# SiLPA_RF_channel.net
KiCad netlist of a schematic drawn in Altium Designer
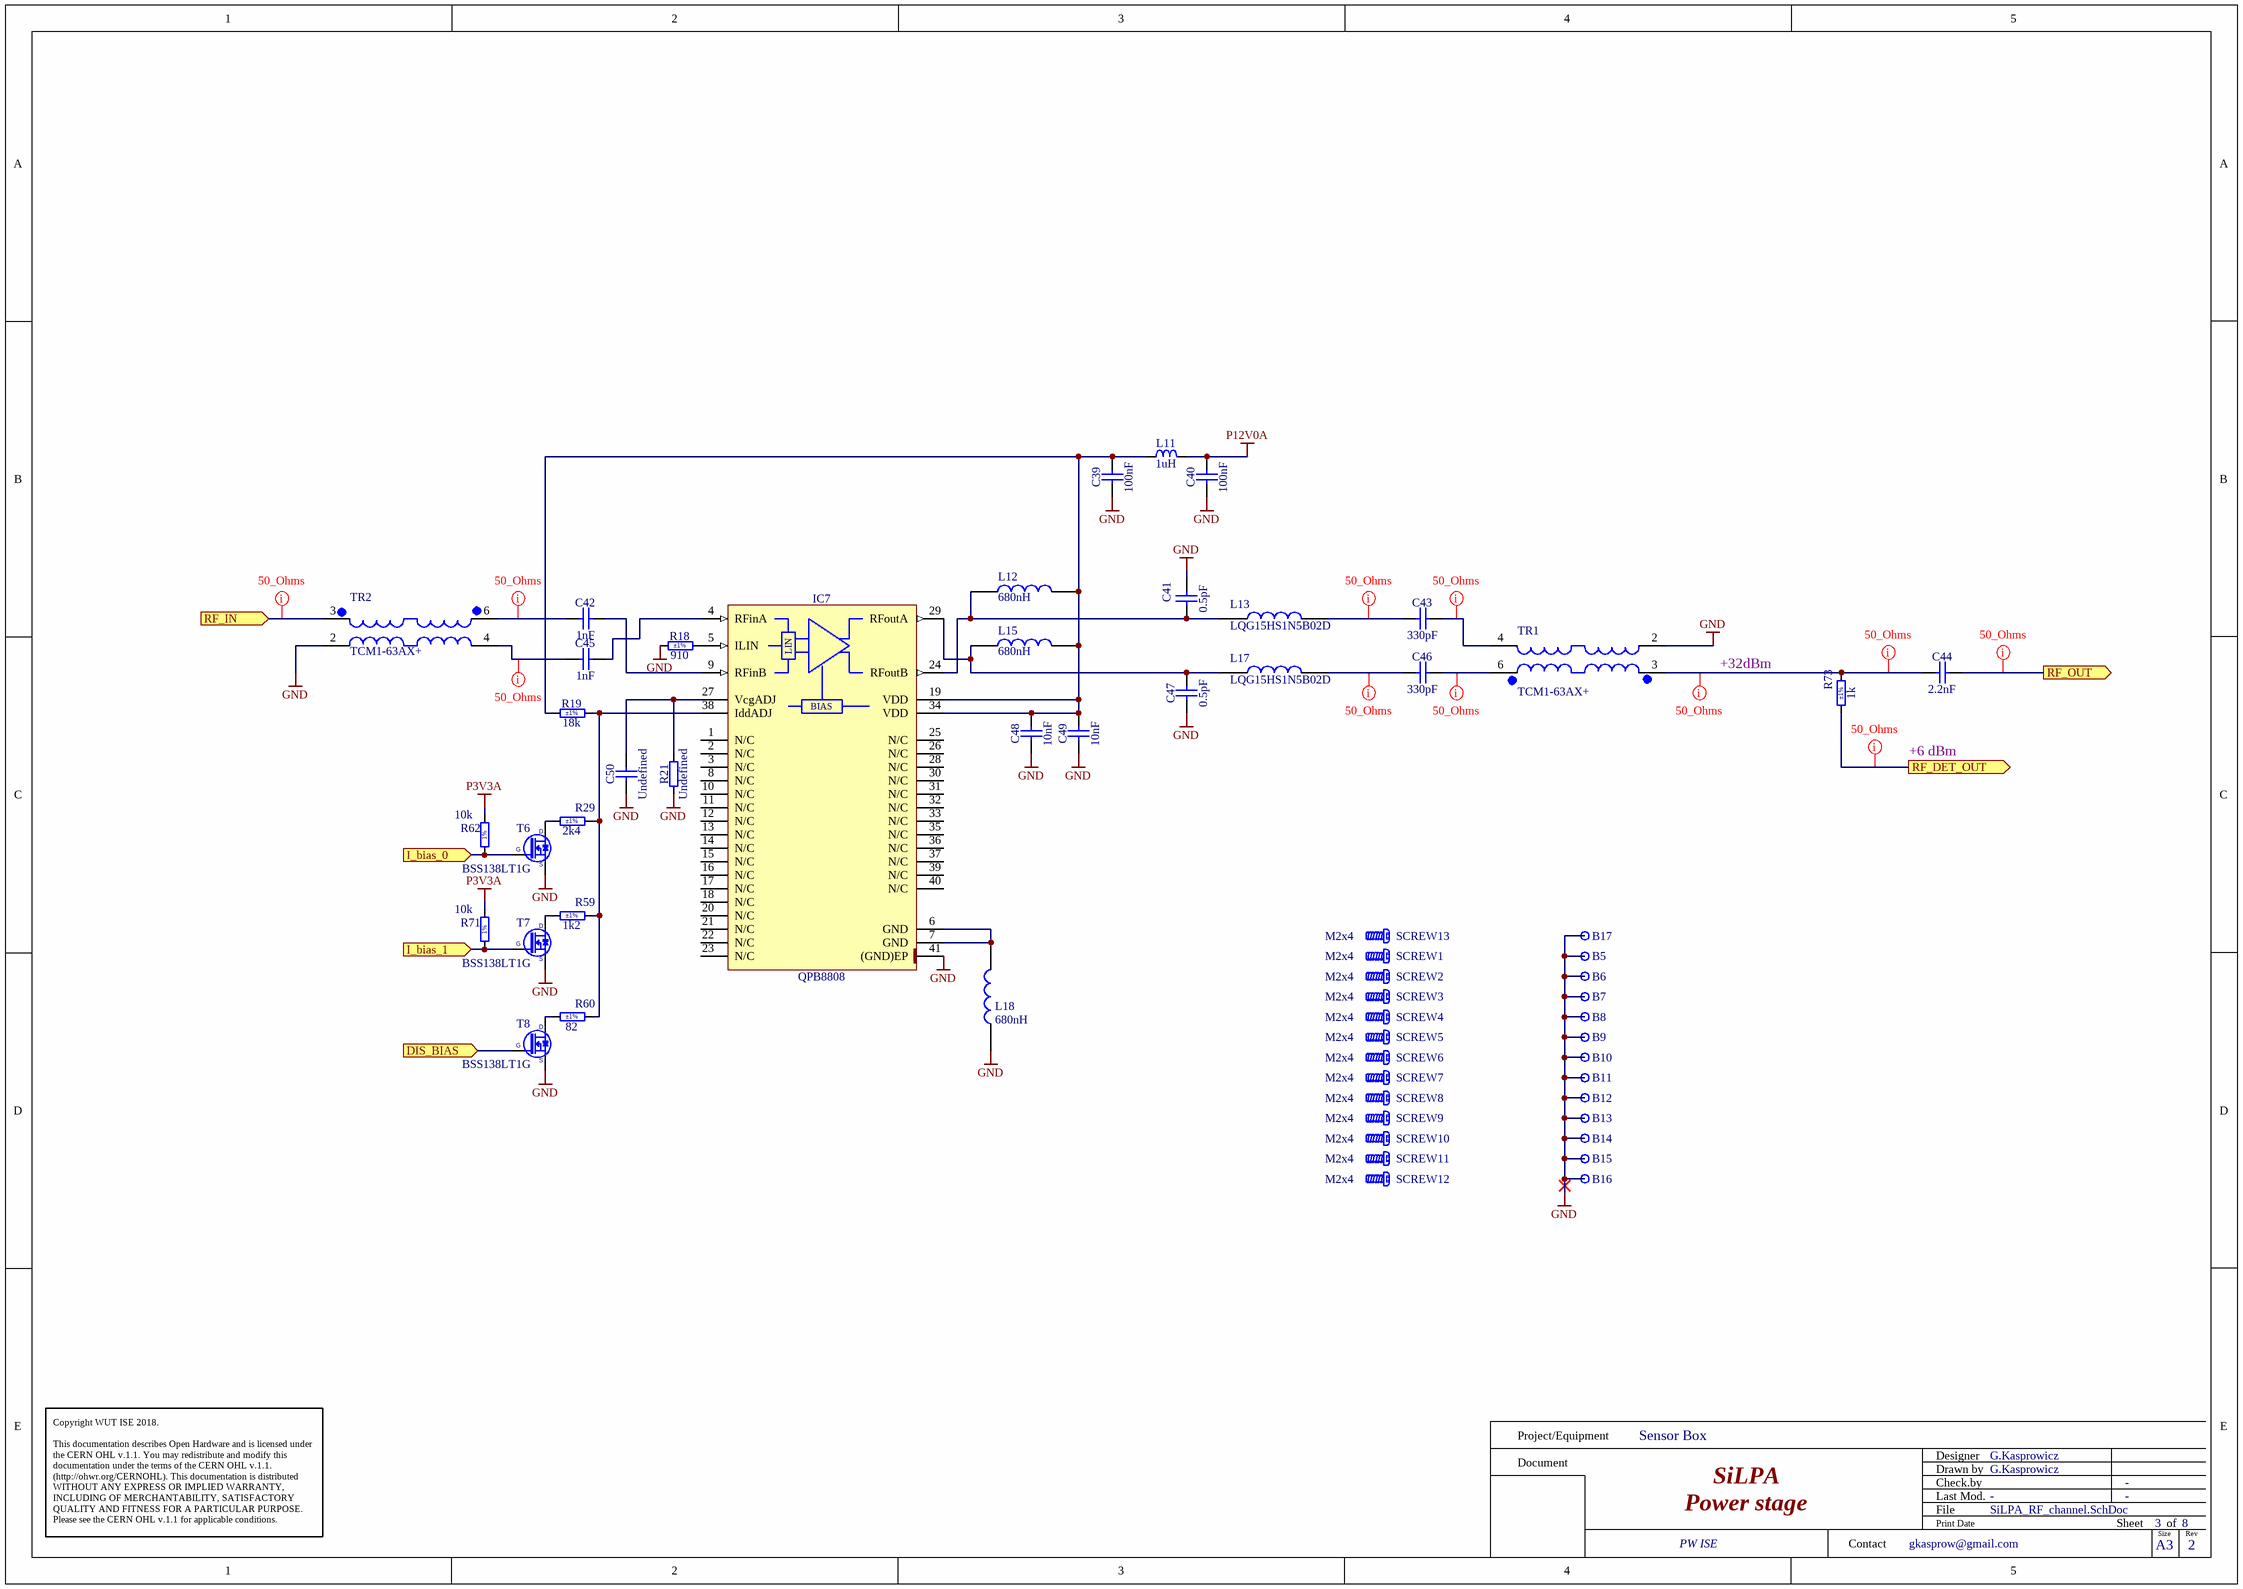
[diagram p0: SiLPA_RF_channel.SchDoc]

(export (version "E")
  (design (tool "Eeschema 10.0.6"))
  (components
    (comp (ref "B5")
      (value "Plated Hole")
      (footprint "MTG240_400")
      (description "Single Terminal Socket")
      (fields (field (name "PART NUMBER") "PLATED_HOLE2.4_PAD4.0") (field (name "AUTHOR") "CERN DEM JMW"))
      (libsource (lib "Eletro-mechanical") (part "Single Terminal Socket"))
    )
    (comp (ref "B6")
      (value "Plated Hole")
      (footprint "MTG240_400")
      (description "Single Terminal Socket")
      (fields (field (name "PART NUMBER") "PLATED_HOLE2.4_PAD4.0") (field (name "AUTHOR") "CERN DEM JMW"))
      (libsource (lib "Eletro-mechanical") (part "Single Terminal Socket"))
    )
    (comp (ref "B7")
      (value "Plated Hole")
      (footprint "MTG240_400")
      (description "Single Terminal Socket")
      (fields (field (name "PART NUMBER") "PLATED_HOLE2.4_PAD4.0") (field (name "AUTHOR") "CERN DEM JMW"))
      (libsource (lib "Eletro-mechanical") (part "Single Terminal Socket"))
    )
    (comp (ref "B8")
      (value "Plated Hole")
      (footprint "MTG240_400")
      (description "Single Terminal Socket")
      (fields (field (name "PART NUMBER") "PLATED_HOLE2.4_PAD4.0") (field (name "AUTHOR") "CERN DEM JMW"))
      (libsource (lib "Eletro-mechanical") (part "Single Terminal Socket"))
    )
    (comp (ref "B9")
      (value "Plated Hole")
      (footprint "MTG240_400")
      (description "Single Terminal Socket")
      (fields (field (name "PART NUMBER") "PLATED_HOLE2.4_PAD4.0") (field (name "AUTHOR") "CERN DEM JMW"))
      (libsource (lib "Eletro-mechanical") (part "Single Terminal Socket"))
    )
    (comp (ref "B10")
      (value "Plated Hole")
      (footprint "MTG240_400")
      (description "Single Terminal Socket")
      (fields (field (name "PART NUMBER") "PLATED_HOLE2.4_PAD4.0") (field (name "AUTHOR") "CERN DEM JMW"))
      (libsource (lib "Eletro-mechanical") (part "Single Terminal Socket"))
    )
    (comp (ref "B11")
      (value "Plated Hole")
      (footprint "MTG240_400")
      (description "Single Terminal Socket")
      (fields (field (name "PART NUMBER") "PLATED_HOLE2.4_PAD4.0") (field (name "AUTHOR") "CERN DEM JMW"))
      (libsource (lib "Eletro-mechanical") (part "Single Terminal Socket"))
    )
    (comp (ref "B12")
      (value "Plated Hole")
      (footprint "MTG240_400")
      (description "Single Terminal Socket")
      (fields (field (name "PART NUMBER") "PLATED_HOLE2.4_PAD4.0") (field (name "AUTHOR") "CERN DEM JMW"))
      (libsource (lib "Eletro-mechanical") (part "Single Terminal Socket"))
    )
    (comp (ref "B13")
      (value "Plated Hole")
      (footprint "MTG240_400")
      (description "Single Terminal Socket")
      (fields (field (name "PART NUMBER") "PLATED_HOLE2.4_PAD4.0") (field (name "AUTHOR") "CERN DEM JMW"))
      (libsource (lib "Eletro-mechanical") (part "Single Terminal Socket"))
    )
    (comp (ref "B14")
      (value "Plated Hole")
      (footprint "MTG240_400")
      (description "Single Terminal Socket")
      (fields (field (name "PART NUMBER") "PLATED_HOLE2.4_PAD4.0") (field (name "AUTHOR") "CERN DEM JMW"))
      (libsource (lib "Eletro-mechanical") (part "Single Terminal Socket"))
    )
    (comp (ref "B15")
      (value "Plated Hole")
      (footprint "MTG240_400")
      (description "Single Terminal Socket")
      (fields (field (name "PART NUMBER") "PLATED_HOLE2.4_PAD4.0") (field (name "AUTHOR") "CERN DEM JMW"))
      (libsource (lib "Eletro-mechanical") (part "Single Terminal Socket"))
    )
    (comp (ref "B16")
      (value "Plated Hole")
      (footprint "MTG240_400")
      (description "Single Terminal Socket")
      (fields (field (name "PART NUMBER") "PLATED_HOLE2.4_PAD4.0") (field (name "AUTHOR") "CERN DEM JMW"))
      (libsource (lib "Eletro-mechanical") (part "Single Terminal Socket"))
    )
    (comp (ref "B17")
      (value "Plated Hole")
      (footprint "MTG240_400")
      (description "Single Terminal Socket")
      (fields (field (name "PART NUMBER") "PLATED_HOLE2.4_PAD4.0") (field (name "AUTHOR") "CERN DEM JMW"))
      (libsource (lib "Eletro-mechanical") (part "Single Terminal Socket"))
    )
    (comp (ref "C39")
      (value "100nF")
      (footprint "CAPC1608X87N")
      (description "Non-polarised capacitor")
      (fields
        (field (name "PART NUMBER") "CC0603_100NF_50V_10%_X7R")
        (field (name "VOLTAGE") "50V")
        (field (name "AUTHOR") "CERN DEM JLC")
      )
      (libsource (lib "Capacitors") (part "Capacitor - non polarized"))
    )
    (comp (ref "C40")
      (value "100nF")
      (footprint "CAPC1608X87N")
      (description "Non-polarised capacitor")
      (fields
        (field (name "PART NUMBER") "CC0603_100NF_50V_10%_X7R")
        (field (name "VOLTAGE") "50V")
        (field (name "AUTHOR") "CERN DEM JLC")
      )
      (libsource (lib "Capacitors") (part "Capacitor - non polarized"))
    )
    (comp (ref "C41")
      (value "0.5pF")
      (footprint "CAPC1608X87N")
      (description "Non-polarised capacitor")
      (fields (field (name "PART NUMBER") "CC0603_0.5PF_50V") (field (name "VOLTAGE") "50V"))
      (libsource (lib "SiLPA") (part "CC0603_0.5PF_50V_WALSIN_HH18N0R5B500CT"))
    )
    (comp (ref "C42")
      (value "1nF")
      (footprint "CAPC1608X90N")
      (description "Non-polarised capacitor")
      (fields
        (field (name "PART NUMBER") "CC0603_1NF_50V_1%_NP0")
        (field (name "VOLTAGE") "50V")
        (field (name "AUTHOR") "CERN DEM JLC")
      )
      (libsource (lib "Capacitors") (part "Capacitor - non polarized"))
    )
    (comp (ref "C43")
      (value "330pF")
      (footprint "CAPC1608X87N")
      (description "Non-polarised capacitor")
      (fields
        (field (name "PART NUMBER") "CC0603_330PF_50V_1%_NP0")
        (field (name "VOLTAGE") "50V")
        (field (name "AUTHOR") "CERN DEM MR")
      )
      (libsource (lib "Capacitors") (part "Capacitor - non polarized"))
    )
    (comp (ref "C44")
      (value "2.2nF")
      (footprint "CAPC1608X87N")
      (description "Non-polarised capacitor")
      (fields
        (field (name "MANUFACTURER") "GENERIC")
        (field (name "MANUFACTURER PART NUMBER") "CC0603_2.2NF_50V_5%_C0G")
        (field (name "AUTHOR") "CERN DEM JMW")
      )
      (libsource (lib "Capacitors") (part "Capacitor - non polarized"))
    )
    (comp (ref "C45")
      (value "1nF")
      (footprint "CAPC1608X90N")
      (description "Non-polarised capacitor")
      (fields
        (field (name "PART NUMBER") "CC0603_1NF_50V_1%_NP0")
        (field (name "VOLTAGE") "50V")
        (field (name "AUTHOR") "CERN DEM JLC")
      )
      (libsource (lib "Capacitors") (part "Capacitor - non polarized"))
    )
    (comp (ref "C46")
      (value "330pF")
      (footprint "CAPC1608X87N")
      (description "Non-polarised capacitor")
      (fields
        (field (name "PART NUMBER") "CC0603_330PF_50V_1%_NP0")
        (field (name "VOLTAGE") "50V")
        (field (name "AUTHOR") "CERN DEM MR")
      )
      (libsource (lib "Capacitors") (part "Capacitor - non polarized"))
    )
    (comp (ref "C47")
      (value "0.5pF")
      (footprint "CAPC1608X87N")
      (description "Non-polarised capacitor")
      (fields (field (name "PART NUMBER") "CC0603_0.5PF_50V") (field (name "VOLTAGE") "50V"))
      (libsource (lib "SiLPA") (part "CC0603_0.5PF_50V_WALSIN_HH18N0R5B500CT"))
    )
    (comp (ref "C48")
      (value "10nF")
      (footprint "CAPC1608X87N")
      (description "Non-polarised capacitor")
      (fields
        (field (name "PART NUMBER") "CC0603_10NF_50V_10%_X7R")
        (field (name "VOLTAGE") "50V")
        (field (name "AUTHOR") "CERN DEM JLC")
      )
      (libsource (lib "Capacitors") (part "Capacitor - non polarized"))
    )
    (comp (ref "C49")
      (value "10nF")
      (footprint "CAPC1608X87N")
      (description "Non-polarised capacitor")
      (fields
        (field (name "PART NUMBER") "CC0603_10NF_50V_10%_X7R")
        (field (name "VOLTAGE") "50V")
        (field (name "AUTHOR") "CERN DEM JLC")
      )
      (libsource (lib "Capacitors") (part "Capacitor - non polarized"))
    )
    (comp (ref "C50")
      (value "Undefined")
      (footprint "CAPC1608X90N")
      (description "Non-polarised capacitor")
      (fields (field (name "PART NUMBER") "CC0603_NO-VALUE") (field (name "AUTHOR") "CERN DEM MR"))
      (libsource (lib "Capacitors") (part "Capacitor - non polarized"))
    )
    (comp (ref "IC7")
      (value "QPB8808")
      (footprint "QFN50P500X700X80-41N-R360X560")
      (description "20 dB CATV +12V Power Doubler")
      (fields (field (name "MANUFACTURER") "QORVO") (field (name "AUTHOR") "CERN DEM BC"))
      (libsource (lib "ICs And Semiconductors") (part "QPB8808"))
    )
    (comp (ref "L11")
      (value "1uH")
      (footprint "INDC2012X110N")
      (description "Inductor")
      (fields
        (field (name "PART NUMBER") "IND0805_1UH_20%_WURTH_74479775210")
        (field (name "POWER") "800mA")
        (field (name "AUTHOR") "CERN DEM JLC")
      )
      (libsource (lib "Inductors & Transformers") (part "Inductor"))
    )
    (comp (ref "L12")
      (value "680nH")
      (footprint "0603AF681XJRW")
      (description "Fixed Inductors 1608 680nH Unshld 5% 490mA 460mOhms")
      (fields
        (field (name "TOLERANCE") "5%")
        (field (name "PART NUMBER") "0603AF-681XJRW")
        (field (name "AUTHORS") "skuchars")
      )
      (libsource (lib "SiLPA") (part "IND0603_COILCRAFT_AF-681XJRW"))
    )
    (comp (ref "L13")
      (value "LQG15HS1N5B02D")
      (footprint "LQG15WH0N7B02D")
      (description "LQG15HS_02 Series Inductor 1.5nH +/-0.1nH 0402 (1005)")
      (fields
        (field (name "POWER") "1000mA")
        (field (name "TOLERANCE") "±0.1nH")
        (field (name "AUTHORS") "skuchars")
      )
      (libsource (lib "SiLPA") (part "LQG15HS1N5B02D"))
    )
    (comp (ref "L15")
      (value "680nH")
      (footprint "0603AF681XJRW")
      (description "Fixed Inductors 1608 680nH Unshld 5% 490mA 460mOhms")
      (fields
        (field (name "TOLERANCE") "5%")
        (field (name "PART NUMBER") "0603AF-681XJRW")
        (field (name "AUTHORS") "skuchars")
      )
      (libsource (lib "SiLPA") (part "IND0603_COILCRAFT_AF-681XJRW"))
    )
    (comp (ref "L17")
      (value "LQG15HS1N5B02D")
      (footprint "LQG15WH0N7B02D")
      (description "LQG15HS_02 Series Inductor 1.5nH +/-0.1nH 0402 (1005)")
      (fields
        (field (name "POWER") "1000mA")
        (field (name "TOLERANCE") "±0.1nH")
        (field (name "AUTHORS") "skuchars")
      )
      (libsource (lib "SiLPA") (part "LQG15HS1N5B02D"))
    )
    (comp (ref "L18")
      (value "680nH")
      (footprint "0603AF681XJRW")
      (description "Fixed Inductors 1608 680nH Unshld 5% 490mA 460mOhms")
      (fields
        (field (name "TOLERANCE") "5%")
        (field (name "PART NUMBER") "0603AF-681XJRW")
        (field (name "AUTHORS") "skuchars")
      )
      (libsource (lib "SiLPA") (part "IND0603_COILCRAFT_AF-681XJRW"))
    )
    (comp (ref "R18")
      (value "910")
      (footprint "RESC1608X55N")
      (description "Resistor - 1%")
      (fields
        (field (name "TOLERANCE") "±1%")
        (field (name "PART NUMBER") "R0603_910R_1%_0.1W_100PPM")
        (field (name "POWER") "0.1W")
        (field (name "AUTHOR") "CERN DEM JLC")
      )
      (libsource (lib "") (part "Resistor - 1%_1"))
    )
    (comp (ref "R19")
      (value "18k")
      (footprint "RESC1005X40N")
      (description "Resistor - 1%")
      (fields
        (field (name "TOLERANCE") "±1%")
        (field (name "PART NUMBER") "R0402_18K_1%_0.0625W_100PPM")
        (field (name "POWER") "0.0625W")
        (field (name "AUTHOR") "CERN DEM JLC")
      )
      (libsource (lib "Resistors") (part "Resistor - 1%"))
    )
    (comp (ref "R21")
      (value "Undefined")
      (footprint "RESC1608X55N")
      (description "Resistor")
      (fields (field (name "PART NUMBER") "R0603_NO-VALUE") (field (name "AUTHOR") "CERN DEM JLC"))
      (libsource (lib "Resistors") (part "Resistor"))
    )
    (comp (ref "R29")
      (value "2k4")
      (footprint "RESC1005X40N")
      (description "Resistor - 1%")
      (fields
        (field (name "TOLERANCE") "±1%")
        (field (name "PART NUMBER") "R0402_2K4_1%_0.0625W_100PPM")
        (field (name "POWER") "0.0625W")
        (field (name "AUTHOR") "CERN DEM JLC")
      )
      (libsource (lib "Resistors") (part "Resistor - 1%"))
    )
    (comp (ref "R59")
      (value "1k2")
      (footprint "RESC1005X40N")
      (description "Resistor - 1%")
      (fields
        (field (name "TOLERANCE") "±1%")
        (field (name "PART NUMBER") "R0402_1K2_1%_0.0625W_100PPM")
        (field (name "POWER") "0.0625W")
        (field (name "AUTHOR") "CERN DEM JLC")
      )
      (libsource (lib "Resistors") (part "Resistor - 1%"))
    )
    (comp (ref "R60")
      (value "82")
      (footprint "RESC1005X40N")
      (description "Resistor - 1%")
      (fields
        (field (name "TOLERANCE") "±1%")
        (field (name "PART NUMBER") "R0402_82R_1%_0.0625W_100PPM")
        (field (name "POWER") "0.0625W")
        (field (name "AUTHOR") "CERN DEM JLC")
      )
      (libsource (lib "Resistors") (part "Resistor - 1%"))
    )
    (comp (ref "R62")
      (value "10k")
      (footprint "RESC1005X40N")
      (description "Resistor - 1%")
      (fields
        (field (name "PART NUMBER") "R0402_10K_1%_0.0625W_100PPM")
        (field (name "POWER") "0.0625W")
        (field (name "AUTHOR") "CERN DEM JLC")
      )
      (libsource (lib "Resistors") (part "Resistor - 1%"))
    )
    (comp (ref "R71")
      (value "10k")
      (footprint "RESC1005X40N")
      (description "Resistor - 1%")
      (fields
        (field (name "PART NUMBER") "R0402_10K_1%_0.0625W_100PPM")
        (field (name "POWER") "0.0625W")
        (field (name "AUTHOR") "CERN DEM JLC")
      )
      (libsource (lib "Resistors") (part "Resistor - 1%"))
    )
    (comp (ref "R73")
      (value "1k")
      (footprint "RESC3216X65N")
      (description "Resistor - 1%")
      (fields
        (field (name "TOLERANCE") "±1%")
        (field (name "PART NUMBER") "R1206_1K_1%_0.25W_100PPM")
        (field (name "POWER") "0.25W")
        (field (name "AUTHOR") "CERN DEM JLC")
      )
      (libsource (lib "") (part "Resistor - 1%_1"))
    )
    (comp (ref "SCREW1")
      (value "M2x4")
      (footprint "BOSSARD_BN5687-3061579_v")
      (description "Screw")
      (fields
        (field (name "PART NUMBER") "BOSSARD_BN5687-3061579_v")
        (field (name "MANUFACTURER") "BOSSARD")
        (field (name "AUTHOR") "CERN DEM JLC")
      )
      (libsource (lib "Eletro-mechanical") (part "Screw"))
    )
    (comp (ref "SCREW2")
      (value "M2x4")
      (footprint "BOSSARD_BN5687-3061579_v")
      (description "Screw")
      (fields
        (field (name "PART NUMBER") "BOSSARD_BN5687-3061579_v")
        (field (name "MANUFACTURER") "BOSSARD")
        (field (name "AUTHOR") "CERN DEM JLC")
      )
      (libsource (lib "Eletro-mechanical") (part "Screw"))
    )
    (comp (ref "SCREW3")
      (value "M2x4")
      (footprint "BOSSARD_BN5687-3061579_v")
      (description "Screw")
      (fields
        (field (name "PART NUMBER") "BOSSARD_BN5687-3061579_v")
        (field (name "MANUFACTURER") "BOSSARD")
        (field (name "AUTHOR") "CERN DEM JLC")
      )
      (libsource (lib "Eletro-mechanical") (part "Screw"))
    )
    (comp (ref "SCREW4")
      (value "M2x4")
      (footprint "BOSSARD_BN5687-3061579_v")
      (description "Screw")
      (fields
        (field (name "PART NUMBER") "BOSSARD_BN5687-3061579_v")
        (field (name "MANUFACTURER") "BOSSARD")
        (field (name "AUTHOR") "CERN DEM JLC")
      )
      (libsource (lib "Eletro-mechanical") (part "Screw"))
    )
    (comp (ref "SCREW5")
      (value "M2x4")
      (footprint "BOSSARD_BN5687-3061579_v")
      (description "Screw")
      (fields
        (field (name "PART NUMBER") "BOSSARD_BN5687-3061579_v")
        (field (name "MANUFACTURER") "BOSSARD")
        (field (name "AUTHOR") "CERN DEM JLC")
      )
      (libsource (lib "Eletro-mechanical") (part "Screw"))
    )
    (comp (ref "SCREW6")
      (value "M2x4")
      (footprint "BOSSARD_BN5687-3061579_v")
      (description "Screw")
      (fields
        (field (name "PART NUMBER") "BOSSARD_BN5687-3061579_v")
        (field (name "MANUFACTURER") "BOSSARD")
        (field (name "AUTHOR") "CERN DEM JLC")
      )
      (libsource (lib "Eletro-mechanical") (part "Screw"))
    )
    (comp (ref "SCREW7")
      (value "M2x4")
      (footprint "BOSSARD_BN5687-3061579_v")
      (description "Screw")
      (fields
        (field (name "PART NUMBER") "BOSSARD_BN5687-3061579_v")
        (field (name "MANUFACTURER") "BOSSARD")
        (field (name "AUTHOR") "CERN DEM JLC")
      )
      (libsource (lib "Eletro-mechanical") (part "Screw"))
    )
    (comp (ref "SCREW8")
      (value "M2x4")
      (footprint "BOSSARD_BN5687-3061579_v")
      (description "Screw")
      (fields
        (field (name "PART NUMBER") "BOSSARD_BN5687-3061579_v")
        (field (name "MANUFACTURER") "BOSSARD")
        (field (name "AUTHOR") "CERN DEM JLC")
      )
      (libsource (lib "Eletro-mechanical") (part "Screw"))
    )
    (comp (ref "SCREW9")
      (value "M2x4")
      (footprint "BOSSARD_BN5687-3061579_v")
      (description "Screw")
      (fields
        (field (name "PART NUMBER") "BOSSARD_BN5687-3061579_v")
        (field (name "MANUFACTURER") "BOSSARD")
        (field (name "AUTHOR") "CERN DEM JLC")
      )
      (libsource (lib "Eletro-mechanical") (part "Screw"))
    )
    (comp (ref "SCREW10")
      (value "M2x4")
      (footprint "BOSSARD_BN5687-3061579_v")
      (description "Screw")
      (fields
        (field (name "PART NUMBER") "BOSSARD_BN5687-3061579_v")
        (field (name "MANUFACTURER") "BOSSARD")
        (field (name "AUTHOR") "CERN DEM JLC")
      )
      (libsource (lib "Eletro-mechanical") (part "Screw"))
    )
    (comp (ref "SCREW11")
      (value "M2x4")
      (footprint "BOSSARD_BN5687-3061579_v")
      (description "Screw")
      (fields
        (field (name "PART NUMBER") "BOSSARD_BN5687-3061579_v")
        (field (name "MANUFACTURER") "BOSSARD")
        (field (name "AUTHOR") "CERN DEM JLC")
      )
      (libsource (lib "Eletro-mechanical") (part "Screw"))
    )
    (comp (ref "SCREW12")
      (value "M2x4")
      (footprint "BOSSARD_BN5687-3061579_v")
      (description "Screw")
      (fields
        (field (name "PART NUMBER") "BOSSARD_BN5687-3061579_v")
        (field (name "MANUFACTURER") "BOSSARD")
        (field (name "AUTHOR") "CERN DEM JLC")
      )
      (libsource (lib "Eletro-mechanical") (part "Screw"))
    )
    (comp (ref "SCREW13")
      (value "M2x4")
      (footprint "BOSSARD_BN5687-3061579_v")
      (description "Screw")
      (fields
        (field (name "PART NUMBER") "BOSSARD_BN5687-3061579_v")
        (field (name "MANUFACTURER") "BOSSARD")
        (field (name "AUTHOR") "CERN DEM JLC")
      )
      (libsource (lib "Eletro-mechanical") (part "Screw"))
    )
    (comp (ref "T6")
      (value "BSS138LT1G")
      (footprint "SOT95P240X110-3N")
      (description "N-CHANNEL MOSFET WITH DIODE")
      (fields (field (name "MANUFACTURER") "ON SEMICONDUCTOR") (field (name "AUTHOR") "CERN DEM JLC"))
      (libsource (lib "ICs And Semiconductors") (part "N-MOSFET-D 1G 2S 3D"))
    )
    (comp (ref "T7")
      (value "BSS138LT1G")
      (footprint "SOT95P240X110-3N")
      (description "N-CHANNEL MOSFET WITH DIODE")
      (fields (field (name "MANUFACTURER") "ON SEMICONDUCTOR") (field (name "AUTHOR") "CERN DEM JLC"))
      (libsource (lib "ICs And Semiconductors") (part "N-MOSFET-D 1G 2S 3D"))
    )
    (comp (ref "T8")
      (value "BSS138LT1G")
      (footprint "SOT95P240X110-3N")
      (description "N-CHANNEL MOSFET WITH DIODE")
      (fields (field (name "MANUFACTURER") "ON SEMICONDUCTOR") (field (name "AUTHOR") "CERN DEM JLC"))
      (libsource (lib "ICs And Semiconductors") (part "N-MOSFET-D 1G 2S 3D"))
    )
    (comp (ref "TR1")
      (value "TCM1-63AX+")
      (footprint "SiLPA:XFMR_TCM1-63AX+")
      (description "1:1 CORE & WIRE Transformer, 10 - 6000 MHz, 50Ω")
      (fields
        (field (name "MANUFACTURER") "Mini-Circuits")
        (field (name "POWER") "0.2W")
        (field (name "AUTHORS") "skuchars")
      )
      (libsource (lib "SiLPA") (part "TCM1-63AX+"))
    )
    (comp (ref "TR2")
      (value "TCM1-63AX+")
      (footprint "SiLPA:XFMR_TCM1-63AX+")
      (description "1:1 CORE & WIRE Transformer, 10 - 6000 MHz, 50Ω")
      (fields
        (field (name "MANUFACTURER") "Mini-Circuits")
        (field (name "POWER") "0.2W")
        (field (name "AUTHORS") "skuchars")
      )
      (libsource (lib "") (part "TCM1-63AX+_1"))
    )
  )
  (nets
    (net (code "1") (name "/DIS_BIAS") (class "Default")
      (node (ref "T8") (pin "1") (pinfunction "G_1") (pintype "passive"))
    )
    (net (code "2") (name "/I_bias_0") (class "Default")
      (node (ref "R62") (pin "1") (pinfunction "1_1") (pintype "passive"))
      (node (ref "T6") (pin "1") (pinfunction "G_1") (pintype "passive"))
    )
    (net (code "3") (name "/I_bias_1") (class "Default")
      (node (ref "R71") (pin "1") (pinfunction "1_1") (pintype "passive"))
      (node (ref "T7") (pin "1") (pinfunction "G_1") (pintype "passive"))
    )
    (net (code "4") (name "/RF_DET_OUT") (class "Default")
      (node (ref "R73") (pin "1") (pinfunction "1_1") (pintype "passive"))
    )
    (net (code "5") (name "/RF_IN") (class "Default")
      (node (ref "TR2") (pin "3") (pinfunction "3_3") (pintype "passive"))
    )
    (net (code "6") (name "/RF_OUT") (class "Default")
      (node (ref "C44") (pin "2") (pinfunction "2_2") (pintype "passive"))
    )
    (net (code "7") (name "GND") (class "Default")
      (node (ref "B10") (pin "1") (pinfunction "1_1") (pintype "bidirectional"))
      (node (ref "B11") (pin "1") (pinfunction "1_1") (pintype "bidirectional"))
      (node (ref "B12") (pin "1") (pinfunction "1_1") (pintype "bidirectional"))
      (node (ref "B13") (pin "1") (pinfunction "1_1") (pintype "bidirectional"))
      (node (ref "B14") (pin "1") (pinfunction "1_1") (pintype "bidirectional"))
      (node (ref "B15") (pin "1") (pinfunction "1_1") (pintype "bidirectional"))
      (node (ref "B16") (pin "1") (pinfunction "1_1") (pintype "bidirectional"))
      (node (ref "B17") (pin "1") (pinfunction "1_1") (pintype "bidirectional"))
      (node (ref "B5") (pin "1") (pinfunction "1_1") (pintype "bidirectional"))
      (node (ref "B6") (pin "1") (pinfunction "1_1") (pintype "bidirectional"))
      (node (ref "B7") (pin "1") (pinfunction "1_1") (pintype "bidirectional"))
      (node (ref "B8") (pin "1") (pinfunction "1_1") (pintype "bidirectional"))
      (node (ref "B9") (pin "1") (pinfunction "1_1") (pintype "bidirectional"))
      (node (ref "C39") (pin "1") (pinfunction "1_1") (pintype "passive"))
      (node (ref "C40") (pin "1") (pinfunction "1_1") (pintype "passive"))
      (node (ref "C41") (pin "2") (pinfunction "2_2") (pintype "passive"))
      (node (ref "C47") (pin "1") (pinfunction "1_1") (pintype "passive"))
      (node (ref "C48") (pin "1") (pinfunction "1_1") (pintype "passive"))
      (node (ref "C49") (pin "1") (pinfunction "1_1") (pintype "passive"))
      (node (ref "C50") (pin "1") (pinfunction "1_1") (pintype "passive"))
      (node (ref "IC7") (pin "41") (pinfunction "(GND)EP_41") (pintype "power_in"))
      (node (ref "L18") (pin "1") (pinfunction "1_1") (pintype "passive"))
      (node (ref "R18") (pin "1") (pinfunction "1_1") (pintype "passive"))
      (node (ref "R21") (pin "1") (pinfunction "1_1") (pintype "passive"))
      (node (ref "T6") (pin "2") (pinfunction "S_2") (pintype "passive"))
      (node (ref "T7") (pin "2") (pinfunction "S_2") (pintype "passive"))
      (node (ref "T8") (pin "2") (pinfunction "S_2") (pintype "passive"))
      (node (ref "TR1") (pin "2") (pinfunction "2_2") (pintype "passive"))
      (node (ref "TR2") (pin "2") (pinfunction "2_2") (pintype "passive"))
    )
    (net (code "8") (name "Net-(C39-Pad2)") (class "Default")
      (node (ref "C39") (pin "2") (pinfunction "2_2") (pintype "passive"))
      (node (ref "C48") (pin "2") (pinfunction "2_2") (pintype "passive"))
      (node (ref "C49") (pin "2") (pinfunction "2_2") (pintype "passive"))
      (node (ref "IC7") (pin "19") (pinfunction "VDD_19") (pintype "power_in"))
      (node (ref "IC7") (pin "34") (pinfunction "VDD_34") (pintype "power_in"))
      (node (ref "L11") (pin "1") (pinfunction "1_1") (pintype "passive"))
      (node (ref "L12") (pin "2") (pinfunction "2_2") (pintype "passive"))
      (node (ref "L15") (pin "2") (pinfunction "2_2") (pintype "passive"))
      (node (ref "R19") (pin "1") (pinfunction "1_1") (pintype "passive"))
    )
    (net (code "9") (name "Net-(C42-Pad1)") (class "Default")
      (node (ref "C42") (pin "1") (pinfunction "1_1") (pintype "passive"))
      (node (ref "TR2") (pin "6") (pinfunction "6_6") (pintype "passive"))
    )
    (net (code "10") (name "Net-(C43-Pad1)") (class "Default")
      (node (ref "C43") (pin "1") (pinfunction "1_1") (pintype "passive"))
      (node (ref "L13") (pin "2") (pinfunction "2_2") (pintype "passive"))
    )
    (net (code "11") (name "Net-(C43-Pad2)") (class "Default")
      (node (ref "C43") (pin "2") (pinfunction "2_2") (pintype "passive"))
      (node (ref "TR1") (pin "4") (pinfunction "4_4") (pintype "passive"))
    )
    (net (code "12") (name "Net-(C44-Pad1)") (class "Default")
      (node (ref "C44") (pin "1") (pinfunction "1_1") (pintype "passive"))
      (node (ref "R73") (pin "2") (pinfunction "2_2") (pintype "passive"))
      (node (ref "TR1") (pin "3") (pinfunction "3_3") (pintype "passive"))
    )
    (net (code "13") (name "Net-(C45-Pad1)") (class "Default")
      (node (ref "C45") (pin "1") (pinfunction "1_1") (pintype "passive"))
      (node (ref "TR2") (pin "4") (pinfunction "4_4") (pintype "passive"))
    )
    (net (code "14") (name "Net-(C46-Pad1)") (class "Default")
      (node (ref "C46") (pin "1") (pinfunction "1_1") (pintype "passive"))
      (node (ref "L17") (pin "2") (pinfunction "2_2") (pintype "passive"))
    )
    (net (code "15") (name "Net-(C46-Pad2)") (class "Default")
      (node (ref "C46") (pin "2") (pinfunction "2_2") (pintype "passive"))
      (node (ref "TR1") (pin "6") (pinfunction "6_6") (pintype "passive"))
    )
    (net (code "16") (name "Net-(IC7-GND-Pad6)") (class "Default")
      (node (ref "IC7") (pin "6") (pinfunction "GND_6") (pintype "power_in"))
      (node (ref "IC7") (pin "7") (pinfunction "GND_7") (pintype "power_in"))
      (node (ref "L18") (pin "2") (pinfunction "2_2") (pintype "passive"))
    )
    (net (code "17") (name "Net-(IC7-ILIN)") (class "Default")
      (node (ref "IC7") (pin "5") (pinfunction "ILIN_5") (pintype "input"))
      (node (ref "R18") (pin "2") (pinfunction "2_2") (pintype "passive"))
    )
    (net (code "18") (name "Net-(IC7-IddADJ)") (class "Default")
      (node (ref "IC7") (pin "38") (pinfunction "IddADJ_38") (pintype "power_in"))
      (node (ref "R19") (pin "2") (pinfunction "2_2") (pintype "passive"))
      (node (ref "R29") (pin "2") (pinfunction "2_2") (pintype "passive"))
      (node (ref "R59") (pin "2") (pinfunction "2_2") (pintype "passive"))
      (node (ref "R60") (pin "2") (pinfunction "2_2") (pintype "passive"))
    )
    (net (code "19") (name "Net-(IC7-RFinA)") (class "Default")
      (node (ref "C45") (pin "2") (pinfunction "2_2") (pintype "passive"))
      (node (ref "IC7") (pin "4") (pinfunction "RFinA_4") (pintype "input"))
    )
    (net (code "20") (name "Net-(IC7-RFinB)") (class "Default")
      (node (ref "C42") (pin "2") (pinfunction "2_2") (pintype "passive"))
      (node (ref "IC7") (pin "9") (pinfunction "RFinB_9") (pintype "input"))
    )
    (net (code "21") (name "Net-(IC7-RFoutA)") (class "Default")
      (node (ref "C47") (pin "2") (pinfunction "2_2") (pintype "passive"))
      (node (ref "IC7") (pin "29") (pinfunction "RFoutA_29") (pintype "output"))
      (node (ref "L15") (pin "1") (pinfunction "1_1") (pintype "passive"))
      (node (ref "L17") (pin "1") (pinfunction "1_1") (pintype "passive"))
    )
    (net (code "22") (name "Net-(IC7-RFoutB)") (class "Default")
      (node (ref "C41") (pin "1") (pinfunction "1_1") (pintype "passive"))
      (node (ref "IC7") (pin "24") (pinfunction "RFoutB_24") (pintype "output"))
      (node (ref "L12") (pin "1") (pinfunction "1_1") (pintype "passive"))
      (node (ref "L13") (pin "1") (pinfunction "1_1") (pintype "passive"))
    )
    (net (code "23") (name "Net-(IC7-VcgADJ)") (class "Default")
      (node (ref "C50") (pin "2") (pinfunction "2_2") (pintype "passive"))
      (node (ref "IC7") (pin "27") (pinfunction "VcgADJ_27") (pintype "power_in"))
      (node (ref "R21") (pin "2") (pinfunction "2_2") (pintype "passive"))
    )
    (net (code "24") (name "Net-(T6-D)") (class "Default")
      (node (ref "R29") (pin "1") (pinfunction "1_1") (pintype "passive"))
      (node (ref "T6") (pin "3") (pinfunction "D_3") (pintype "passive"))
    )
    (net (code "25") (name "Net-(T7-D)") (class "Default")
      (node (ref "R59") (pin "1") (pinfunction "1_1") (pintype "passive"))
      (node (ref "T7") (pin "3") (pinfunction "D_3") (pintype "passive"))
    )
    (net (code "26") (name "Net-(T8-D)") (class "Default")
      (node (ref "R60") (pin "1") (pinfunction "1_1") (pintype "passive"))
      (node (ref "T8") (pin "3") (pinfunction "D_3") (pintype "passive"))
    )
    (net (code "27") (name "P3V3A") (class "Default")
      (node (ref "R62") (pin "2") (pinfunction "2_2") (pintype "passive"))
      (node (ref "R71") (pin "2") (pinfunction "2_2") (pintype "passive"))
    )
    (net (code "28") (name "P12V0A") (class "Default")
      (node (ref "C40") (pin "2") (pinfunction "2_2") (pintype "passive"))
      (node (ref "L11") (pin "2") (pinfunction "2_2") (pintype "passive"))
    )
    (net (code "29") (name "unconnected-(IC7-N{slash}C-Pad1)") (class "Default")
      (node (ref "IC7") (pin "1") (pinfunction "N/C_1") (pintype "passive"))
    )
    (net (code "30") (name "unconnected-(IC7-N{slash}C-Pad2)") (class "Default")
      (node (ref "IC7") (pin "2") (pinfunction "N/C_2") (pintype "passive"))
    )
    (net (code "31") (name "unconnected-(IC7-N{slash}C-Pad3)") (class "Default")
      (node (ref "IC7") (pin "3") (pinfunction "N/C_3") (pintype "passive"))
    )
    (net (code "32") (name "unconnected-(IC7-N{slash}C-Pad8)") (class "Default")
      (node (ref "IC7") (pin "8") (pinfunction "N/C_8") (pintype "passive"))
    )
    (net (code "33") (name "unconnected-(IC7-N{slash}C-Pad10)") (class "Default")
      (node (ref "IC7") (pin "10") (pinfunction "N/C_10") (pintype "passive"))
    )
    (net (code "34") (name "unconnected-(IC7-N{slash}C-Pad11)") (class "Default")
      (node (ref "IC7") (pin "11") (pinfunction "N/C_11") (pintype "passive"))
    )
    (net (code "35") (name "unconnected-(IC7-N{slash}C-Pad12)") (class "Default")
      (node (ref "IC7") (pin "12") (pinfunction "N/C_12") (pintype "passive"))
    )
    (net (code "36") (name "unconnected-(IC7-N{slash}C-Pad13)") (class "Default")
      (node (ref "IC7") (pin "13") (pinfunction "N/C_13") (pintype "passive"))
    )
    (net (code "37") (name "unconnected-(IC7-N{slash}C-Pad14)") (class "Default")
      (node (ref "IC7") (pin "14") (pinfunction "N/C_14") (pintype "passive"))
    )
    (net (code "38") (name "unconnected-(IC7-N{slash}C-Pad15)") (class "Default")
      (node (ref "IC7") (pin "15") (pinfunction "N/C_15") (pintype "passive"))
    )
    (net (code "39") (name "unconnected-(IC7-N{slash}C-Pad16)") (class "Default")
      (node (ref "IC7") (pin "16") (pinfunction "N/C_16") (pintype "passive"))
    )
    (net (code "40") (name "unconnected-(IC7-N{slash}C-Pad17)") (class "Default")
      (node (ref "IC7") (pin "17") (pinfunction "N/C_17") (pintype "passive"))
    )
    (net (code "41") (name "unconnected-(IC7-N{slash}C-Pad18)") (class "Default")
      (node (ref "IC7") (pin "18") (pinfunction "N/C_18") (pintype "passive"))
    )
    (net (code "42") (name "unconnected-(IC7-N{slash}C-Pad20)") (class "Default")
      (node (ref "IC7") (pin "20") (pinfunction "N/C_20") (pintype "passive"))
    )
    (net (code "43") (name "unconnected-(IC7-N{slash}C-Pad21)") (class "Default")
      (node (ref "IC7") (pin "21") (pinfunction "N/C_21") (pintype "passive"))
    )
    (net (code "44") (name "unconnected-(IC7-N{slash}C-Pad22)") (class "Default")
      (node (ref "IC7") (pin "22") (pinfunction "N/C_22") (pintype "passive"))
    )
    (net (code "45") (name "unconnected-(IC7-N{slash}C-Pad23)") (class "Default")
      (node (ref "IC7") (pin "23") (pinfunction "N/C_23") (pintype "passive"))
    )
    (net (code "46") (name "unconnected-(IC7-N{slash}C-Pad25)") (class "Default")
      (node (ref "IC7") (pin "25") (pinfunction "N/C_25") (pintype "passive"))
    )
    (net (code "47") (name "unconnected-(IC7-N{slash}C-Pad26)") (class "Default")
      (node (ref "IC7") (pin "26") (pinfunction "N/C_26") (pintype "passive"))
    )
    (net (code "48") (name "unconnected-(IC7-N{slash}C-Pad28)") (class "Default")
      (node (ref "IC7") (pin "28") (pinfunction "N/C_28") (pintype "passive"))
    )
    (net (code "49") (name "unconnected-(IC7-N{slash}C-Pad30)") (class "Default")
      (node (ref "IC7") (pin "30") (pinfunction "N/C_30") (pintype "passive"))
    )
    (net (code "50") (name "unconnected-(IC7-N{slash}C-Pad31)") (class "Default")
      (node (ref "IC7") (pin "31") (pinfunction "N/C_31") (pintype "passive"))
    )
    (net (code "51") (name "unconnected-(IC7-N{slash}C-Pad32)") (class "Default")
      (node (ref "IC7") (pin "32") (pinfunction "N/C_32") (pintype "passive"))
    )
    (net (code "52") (name "unconnected-(IC7-N{slash}C-Pad33)") (class "Default")
      (node (ref "IC7") (pin "33") (pinfunction "N/C_33") (pintype "passive"))
    )
    (net (code "53") (name "unconnected-(IC7-N{slash}C-Pad35)") (class "Default")
      (node (ref "IC7") (pin "35") (pinfunction "N/C_35") (pintype "passive"))
    )
    (net (code "54") (name "unconnected-(IC7-N{slash}C-Pad36)") (class "Default")
      (node (ref "IC7") (pin "36") (pinfunction "N/C_36") (pintype "passive"))
    )
    (net (code "55") (name "unconnected-(IC7-N{slash}C-Pad37)") (class "Default")
      (node (ref "IC7") (pin "37") (pinfunction "N/C_37") (pintype "passive"))
    )
    (net (code "56") (name "unconnected-(IC7-N{slash}C-Pad39)") (class "Default")
      (node (ref "IC7") (pin "39") (pinfunction "N/C_39") (pintype "passive"))
    )
    (net (code "57") (name "unconnected-(IC7-N{slash}C-Pad40)") (class "Default")
      (node (ref "IC7") (pin "40") (pinfunction "N/C_40") (pintype "passive"))
    )
  )
)
